# RasPi-BplusHAT_CamSlot.net
KiCad netlist of a schematic drawn in EAGLE
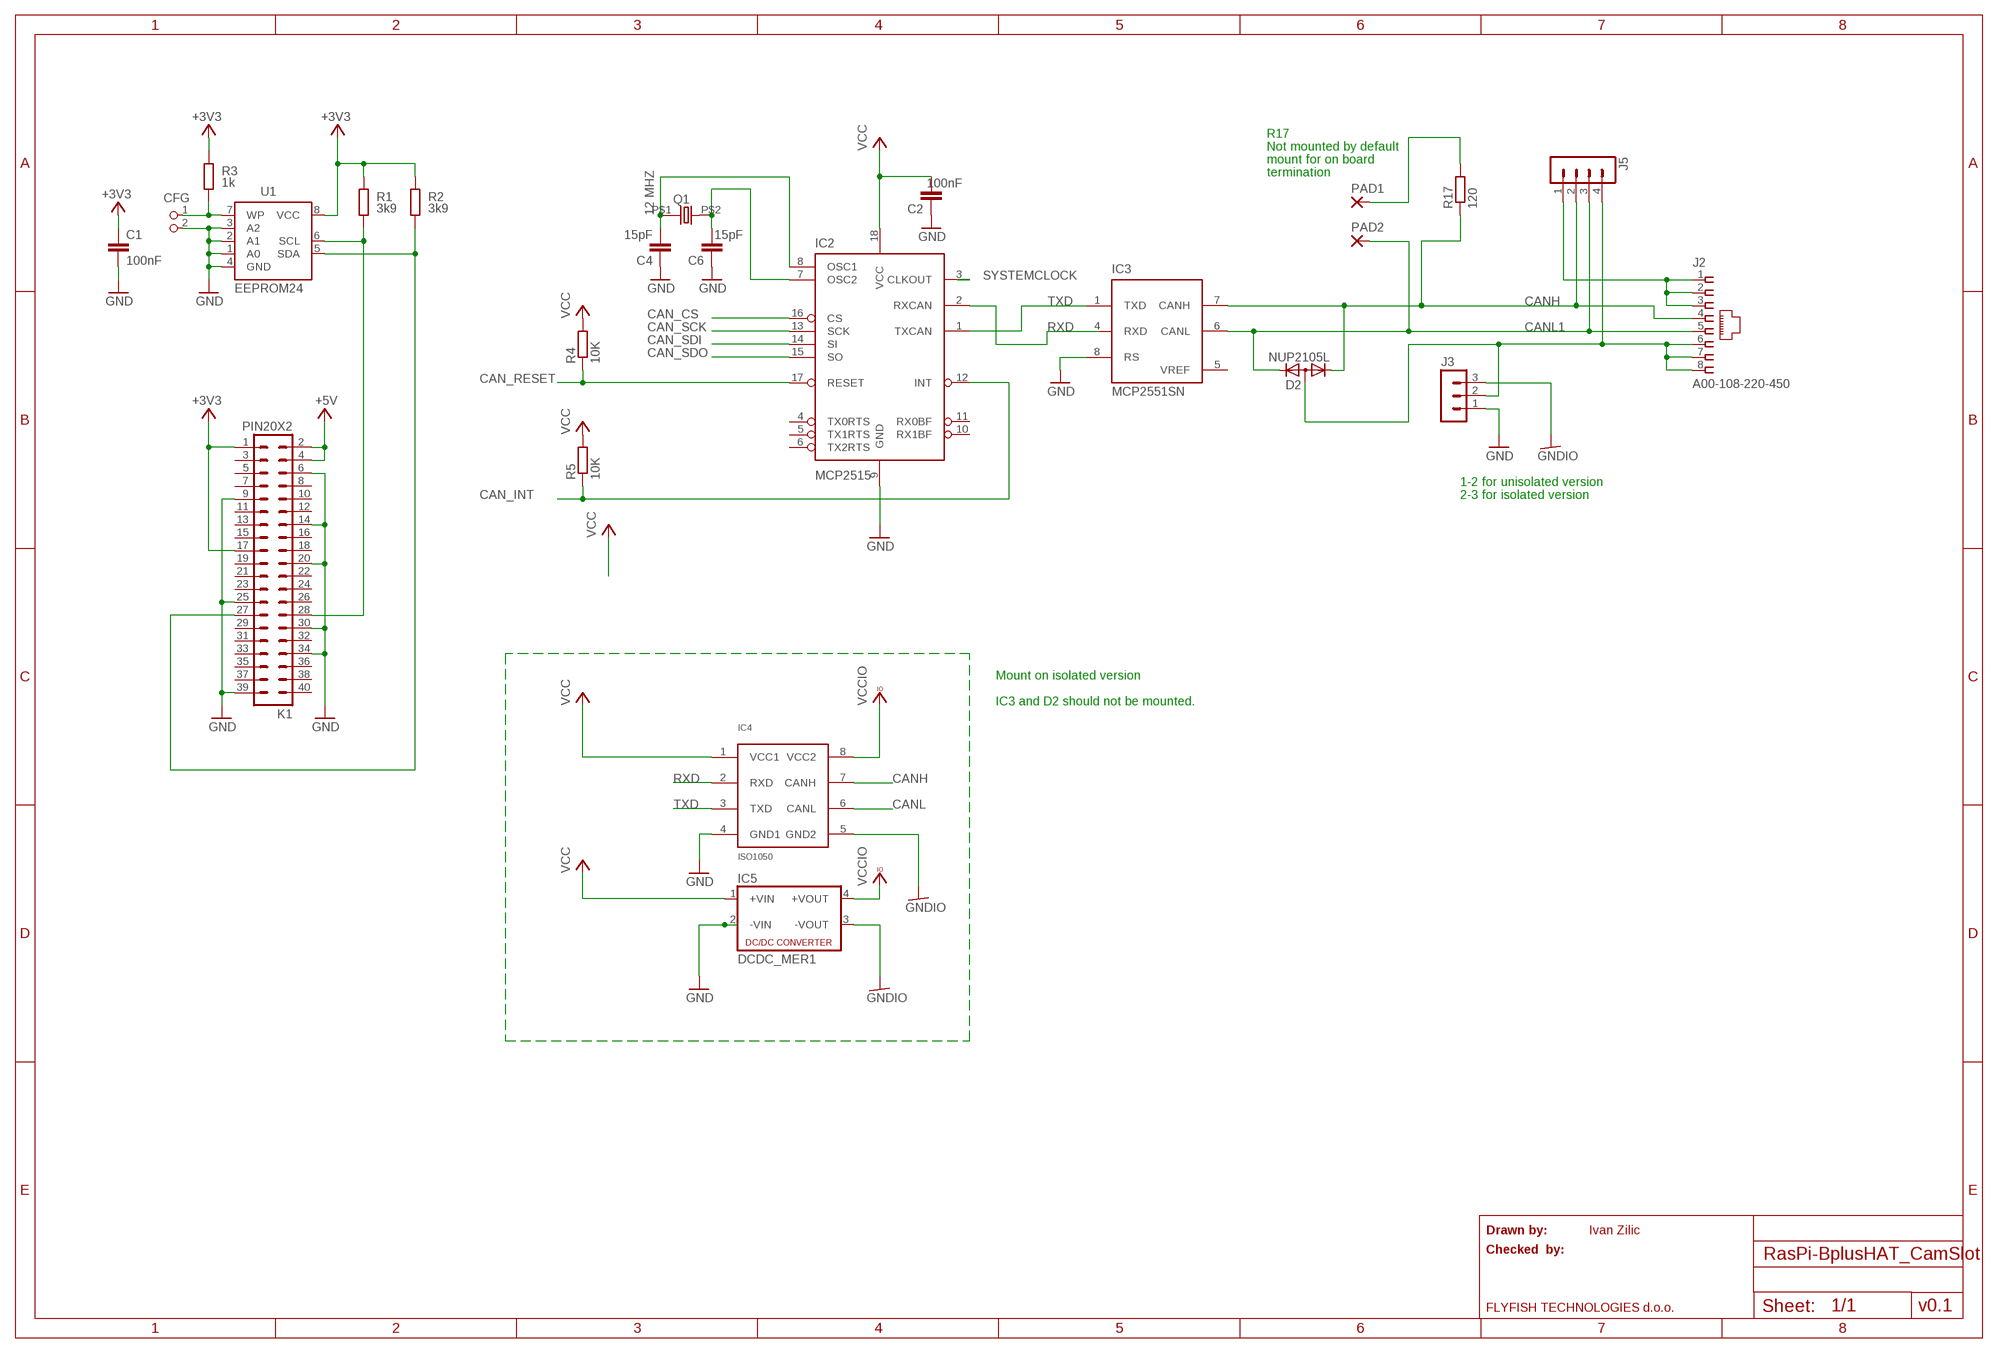
[diagram p0: schematic, sheet 1]

(export (version "E")
  (design (tool "Eeschema 10.0.6"))
  (components
    (comp (ref "C1")
      (value "100nF")
      (footprint "eagle-import:C0805K")
      (libsource (lib "eagle-import") (part "resistor_C-EUC0805K"))
    )
    (comp (ref "C2")
      (value "100nF")
      (footprint "eagle-import:C0805")
      (libsource (lib "eagle-import") (part "C-EUC0805"))
    )
    (comp (ref "C4")
      (value "15pF")
      (footprint "eagle-import:C0805")
      (libsource (lib "eagle-import") (part "C-EUC0805"))
    )
    (comp (ref "C6")
      (value "15pF")
      (footprint "eagle-import:C0805")
      (libsource (lib "eagle-import") (part "C-EUC0805"))
    )
    (comp (ref "CFG")
      (value "PIN2_100")
      (footprint "eagle-import:PIN_W_2")
      (libsource (lib "eagle-import") (part "PIN2_100"))
    )
    (comp (ref "D2")
      (value "NUP2105L")
      (footprint "eagle-import:SOT23")
      (libsource (lib "eagle-import") (part "DIODE-2CA|ACSOT23"))
    )
    (comp (ref "IC2")
      (value "MCP2515")
      (footprint "eagle-import:SO-18W")
      (libsource (lib "eagle-import") (part "MCP2515"))
    )
    (comp (ref "IC3")
      (value "MCP2551SN")
      (footprint "eagle-import:SO-08")
      (libsource (lib "eagle-import") (part "MCP2551SN"))
    )
    (comp (ref "IC4")
      (value "ISO1050")
      (footprint "eagle-import:DUB_PSOP")
      (libsource (lib "eagle-import") (part "ISO1050"))
    )
    (comp (ref "IC5")
      (value "DCDC_MER1")
      (footprint "eagle-import:MER1")
      (libsource (lib "eagle-import") (part "DCDC_MER1"))
    )
    (comp (ref "J2")
      (value "A00-108-220-450")
      (footprint "eagle-import:RJ-45")
      (libsource (lib "eagle-import") (part "A00-108-220-450"))
    )
    (comp (ref "J3")
      (value "MA03-1")
      (footprint "eagle-import:MA03-1")
      (libsource (lib "eagle-import") (part "MA03-1"))
    )
    (comp (ref "J5")
      (value "MA04-1")
      (footprint "eagle-import:MA04-1")
      (libsource (lib "eagle-import") (part "MA04-1"))
    )
    (comp (ref "K1")
      (value "PIN20X2")
      (footprint "eagle-import:PIN_20X2")
      (libsource (lib "eagle-import") (part "PIN20X2"))
    )
    (comp (ref "PAD1")
      (value "1,6/0,8")
      (footprint "eagle-import:1,6_0,8")
      (libsource (lib "eagle-import") (part "1,6/0,8"))
    )
    (comp (ref "PAD2")
      (value "1,6/0,8")
      (footprint "eagle-import:1,6_0,8")
      (libsource (lib "eagle-import") (part "1,6/0,8"))
    )
    (comp (ref "Q1")
      (value "12 MHZ")
      (footprint "eagle-import:9C")
      (libsource (lib "eagle-import") (part "HC-49S"))
    )
    (comp (ref "R1")
      (value "3k9")
      (footprint "eagle-import:M0805")
      (fields (field (name "TOLERANCE") "5%"))
      (libsource (lib "eagle-import") (part "resistor_R-EU_M0805"))
    )
    (comp (ref "R2")
      (value "3k9")
      (footprint "eagle-import:M0805")
      (fields (field (name "TOLERANCE") "5%"))
      (libsource (lib "eagle-import") (part "resistor_R-EU_M0805"))
    )
    (comp (ref "R3")
      (value "1k")
      (footprint "eagle-import:M0805")
      (fields (field (name "TOLERANCE") "5%"))
      (libsource (lib "eagle-import") (part "resistor_R-EU_M0805"))
    )
    (comp (ref "R4")
      (value "10K")
      (footprint "eagle-import:R0805")
      (libsource (lib "eagle-import") (part "R-EU_R0805"))
    )
    (comp (ref "R5")
      (value "10K")
      (footprint "eagle-import:R0805")
      (libsource (lib "eagle-import") (part "R-EU_R0805"))
    )
    (comp (ref "R17")
      (value "120")
      (footprint "eagle-import:R0805")
      (libsource (lib "eagle-import") (part "R-EU_R0805"))
    )
    (comp (ref "U1")
      (value "EEPROM24")
      (footprint "eagle-import:SOIC8")
      (libsource (lib "eagle-import") (part "EEPROM24"))
    )
  )
  (nets
    (net (code "1") (name "+3V3") (class "Default")
      (node (ref "C1") (pin "1") (pinfunction "1_1") (pintype "passive"))
      (node (ref "K1") (pin "1") (pinfunction "1_1") (pintype "passive"))
      (node (ref "K1") (pin "17") (pinfunction "17_17") (pintype "passive"))
      (node (ref "R1") (pin "2") (pinfunction "2_2") (pintype "passive"))
      (node (ref "R2") (pin "2") (pinfunction "2_2") (pintype "passive"))
      (node (ref "R3") (pin "2") (pinfunction "2_2") (pintype "passive"))
      (node (ref "U1") (pin "8") (pinfunction "VCC_8") (pintype "power_in"))
    )
    (net (code "2") (name "+5V") (class "Default")
      (node (ref "K1") (pin "2") (pinfunction "2_2") (pintype "passive"))
      (node (ref "K1") (pin "4") (pinfunction "4_4") (pintype "passive"))
    )
    (net (code "3") (name "/CANH") (class "Default")
      (node (ref "D2") (pin "1") (pinfunction "K1_1") (pintype "passive"))
      (node (ref "IC3") (pin "7") (pinfunction "CANH_7") (pintype "bidirectional"))
      (node (ref "IC4") (pin "7") (pinfunction "CANH_7") (pintype "bidirectional"))
      (node (ref "J2") (pin "4") (pinfunction "4_4") (pintype "passive"))
      (node (ref "J5") (pin "2") (pinfunction "2_2") (pintype "passive"))
      (node (ref "R17") (pin "1") (pinfunction "1_1") (pintype "passive"))
    )
    (net (code "4") (name "/CANL") (class "Default")
      (node (ref "IC4") (pin "6") (pinfunction "CANL_6") (pintype "bidirectional"))
    )
    (net (code "5") (name "/CANL1") (class "Default")
      (node (ref "D2") (pin "2") (pinfunction "K2_2") (pintype "passive"))
      (node (ref "IC3") (pin "6") (pinfunction "CANL_6") (pintype "bidirectional"))
      (node (ref "J2") (pin "5") (pinfunction "5_5") (pintype "passive"))
      (node (ref "J5") (pin "3") (pinfunction "3_3") (pintype "passive"))
      (node (ref "PAD2") (pin "1") (pinfunction "P_1") (pintype "passive"))
    )
    (net (code "6") (name "/CAN_CS") (class "Default")
      (node (ref "IC2") (pin "16") (pinfunction "CS_16") (pintype "input"))
    )
    (net (code "7") (name "/CAN_INT") (class "Default")
      (node (ref "IC2") (pin "12") (pinfunction "INT_12") (pintype "output"))
      (node (ref "R5") (pin "1") (pinfunction "1_1") (pintype "passive"))
    )
    (net (code "8") (name "/CAN_RESET") (class "Default")
      (node (ref "IC2") (pin "17") (pinfunction "RESET_17") (pintype "input"))
      (node (ref "R4") (pin "1") (pinfunction "1_1") (pintype "passive"))
    )
    (net (code "9") (name "/CAN_SCK") (class "Default")
      (node (ref "IC2") (pin "13") (pinfunction "SCK_13") (pintype "input"))
    )
    (net (code "10") (name "/CAN_SDI") (class "Default")
      (node (ref "IC2") (pin "14") (pinfunction "SI_14") (pintype "input"))
    )
    (net (code "11") (name "/CAN_SDO") (class "Default")
      (node (ref "IC2") (pin "15") (pinfunction "SO_15") (pintype "output"))
    )
    (net (code "12") (name "/RXD") (class "Default")
      (node (ref "IC2") (pin "2") (pinfunction "RXCAN_2") (pintype "input"))
      (node (ref "IC4") (pin "2") (pinfunction "RXD_2") (pintype "bidirectional"))
    )
    (net (code "13") (name "/SYSTEMCLOCK") (class "Default")
      (node (ref "IC2") (pin "3") (pinfunction "CLKOUT_3") (pintype "output"))
    )
    (net (code "14") (name "/TXD") (class "Default")
      (node (ref "IC2") (pin "1") (pinfunction "TXCAN_1") (pintype "output"))
      (node (ref "IC3") (pin "1") (pinfunction "TXD_1") (pintype "input"))
      (node (ref "IC4") (pin "3") (pinfunction "TXD_3") (pintype "bidirectional"))
    )
    (net (code "15") (name "/VREF") (class "Default")
      (node (ref "IC3") (pin "5") (pinfunction "VREF_5") (pintype "power_in"))
    )
    (net (code "16") (name "GND") (class "Default")
      (node (ref "C1") (pin "2") (pinfunction "2_2") (pintype "passive"))
      (node (ref "C2") (pin "1") (pinfunction "1_1") (pintype "passive"))
      (node (ref "C4") (pin "1") (pinfunction "1_1") (pintype "passive"))
      (node (ref "C6") (pin "1") (pinfunction "1_1") (pintype "passive"))
      (node (ref "CFG") (pin "2") (pinfunction "2_2") (pintype "passive"))
      (node (ref "IC2") (pin "9") (pinfunction "GND_9") (pintype "power_in"))
      (node (ref "IC3") (pin "8") (pinfunction "RS_8") (pintype "input"))
      (node (ref "IC4") (pin "4") (pinfunction "GND1_4") (pintype "power_in"))
      (node (ref "IC5") (pin "2") (pinfunction "-VIN_2") (pintype "passive"))
      (node (ref "J3") (pin "1") (pinfunction "1_1") (pintype "passive"))
      (node (ref "K1") (pin "14") (pinfunction "14_14") (pintype "passive"))
      (node (ref "K1") (pin "20") (pinfunction "20_20") (pintype "passive"))
      (node (ref "K1") (pin "25") (pinfunction "25_25") (pintype "passive"))
      (node (ref "K1") (pin "30") (pinfunction "30_30") (pintype "passive"))
      (node (ref "K1") (pin "34") (pinfunction "34_34") (pintype "passive"))
      (node (ref "K1") (pin "39") (pinfunction "39_39") (pintype "passive"))
      (node (ref "K1") (pin "6") (pinfunction "6_6") (pintype "passive"))
      (node (ref "K1") (pin "9") (pinfunction "9_9") (pintype "passive"))
      (node (ref "U1") (pin "1") (pinfunction "A0_1") (pintype "input"))
      (node (ref "U1") (pin "2") (pinfunction "A1_2") (pintype "input"))
      (node (ref "U1") (pin "3") (pinfunction "A2_3") (pintype "input"))
      (node (ref "U1") (pin "4") (pinfunction "GND_4") (pintype "power_in"))
    )
    (net (code "17") (name "GNDIO") (class "Default")
      (node (ref "IC4") (pin "5") (pinfunction "GND2_5") (pintype "power_in"))
      (node (ref "IC5") (pin "3") (pinfunction "-VOUT_3") (pintype "passive"))
      (node (ref "J3") (pin "3") (pinfunction "3_3") (pintype "passive"))
    )
    (net (code "18") (name "Net-(D2-A)") (class "Default")
      (node (ref "D2") (pin "3") (pinfunction "A_3") (pintype "passive"))
      (node (ref "J2") (pin "6") (pinfunction "6_6") (pintype "passive"))
      (node (ref "J2") (pin "7") (pinfunction "7_7") (pintype "passive"))
      (node (ref "J2") (pin "8") (pinfunction "8_8") (pintype "passive"))
      (node (ref "J3") (pin "2") (pinfunction "2_2") (pintype "passive"))
      (node (ref "J5") (pin "4") (pinfunction "4_4") (pintype "passive"))
    )
    (net (code "19") (name "Net-(IC2-OSC1)") (class "Default")
      (node (ref "C4") (pin "2") (pinfunction "2_2") (pintype "passive"))
      (node (ref "IC2") (pin "8") (pinfunction "OSC1_8") (pintype "input"))
      (node (ref "Q1") (pin "P$1") (pinfunction "1_P$1") (pintype "passive"))
    )
    (net (code "20") (name "Net-(IC2-OSC2)") (class "Default")
      (node (ref "C6") (pin "2") (pinfunction "2_2") (pintype "passive"))
      (node (ref "IC2") (pin "7") (pinfunction "OSC2_7") (pintype "output"))
      (node (ref "Q1") (pin "P$2") (pinfunction "2_P$2") (pintype "passive"))
    )
    (net (code "21") (name "Net-(J2-Pad1)") (class "Default")
      (node (ref "J2") (pin "1") (pinfunction "1_1") (pintype "passive"))
      (node (ref "J2") (pin "2") (pinfunction "2_2") (pintype "passive"))
      (node (ref "J2") (pin "3") (pinfunction "3_3") (pintype "passive"))
      (node (ref "J5") (pin "1") (pinfunction "1_1") (pintype "passive"))
    )
    (net (code "22") (name "Net-(PAD1-P)") (class "Default")
      (node (ref "PAD1") (pin "1") (pinfunction "P_1") (pintype "passive"))
      (node (ref "R17") (pin "2") (pinfunction "2_2") (pintype "passive"))
    )
    (net (code "23") (name "Net-(U1-SCL)") (class "Default")
      (node (ref "K1") (pin "28") (pinfunction "28_28") (pintype "passive"))
      (node (ref "R1") (pin "1") (pinfunction "1_1") (pintype "passive"))
      (node (ref "U1") (pin "6") (pinfunction "SCL_6") (pintype "input"))
    )
    (net (code "24") (name "Net-(U1-SDA)") (class "Default")
      (node (ref "K1") (pin "27") (pinfunction "27_27") (pintype "passive"))
      (node (ref "R2") (pin "1") (pinfunction "1_1") (pintype "passive"))
      (node (ref "U1") (pin "5") (pinfunction "SDA_5") (pintype "bidirectional"))
    )
    (net (code "25") (name "Net-(U1-WP)") (class "Default")
      (node (ref "CFG") (pin "1") (pinfunction "1_1") (pintype "passive"))
      (node (ref "R3") (pin "1") (pinfunction "1_1") (pintype "passive"))
      (node (ref "U1") (pin "7") (pinfunction "WP_7") (pintype "input"))
    )
    (net (code "26") (name "VCC") (class "Default")
      (node (ref "C2") (pin "2") (pinfunction "2_2") (pintype "passive"))
      (node (ref "IC2") (pin "18") (pinfunction "VCC_18") (pintype "power_in"))
      (node (ref "IC4") (pin "1") (pinfunction "VCC1_1") (pintype "power_in"))
      (node (ref "IC5") (pin "1") (pinfunction "+VIN_1") (pintype "passive"))
      (node (ref "R4") (pin "2") (pinfunction "2_2") (pintype "passive"))
      (node (ref "R5") (pin "2") (pinfunction "2_2") (pintype "passive"))
    )
    (net (code "27") (name "VCCIO") (class "Default")
      (node (ref "IC4") (pin "8") (pinfunction "VCC2_8") (pintype "power_in"))
      (node (ref "IC5") (pin "4") (pinfunction "+VOUT_4") (pintype "passive"))
    )
    (net (code "28") (name "unconnected-(IC2-RX0BF-Pad11)") (class "Default")
      (node (ref "IC2") (pin "11") (pinfunction "RX0BF_11") (pintype "output"))
    )
    (net (code "29") (name "unconnected-(IC2-RX1BF-Pad10)") (class "Default")
      (node (ref "IC2") (pin "10") (pinfunction "RX1BF_10") (pintype "output"))
    )
    (net (code "30") (name "unconnected-(IC2-TX0RTS-Pad4)") (class "Default")
      (node (ref "IC2") (pin "4") (pinfunction "TX0RTS_4") (pintype "input"))
    )
    (net (code "31") (name "unconnected-(IC2-TX1RTS-Pad5)") (class "Default")
      (node (ref "IC2") (pin "5") (pinfunction "TX1RTS_5") (pintype "input"))
    )
    (net (code "32") (name "unconnected-(IC2-TX2RTS-Pad6)") (class "Default")
      (node (ref "IC2") (pin "6") (pinfunction "TX2RTS_6") (pintype "input"))
    )
    (net (code "33") (name "unconnected-(IC3A-RXD-Pad4)") (class "Default")
      (node (ref "IC3") (pin "4") (pinfunction "RXD_4") (pintype "output"))
    )
    (net (code "34") (name "unconnected-(K1-Pad3)") (class "Default")
      (node (ref "K1") (pin "3") (pinfunction "3_3") (pintype "passive"))
    )
    (net (code "35") (name "unconnected-(K1-Pad5)") (class "Default")
      (node (ref "K1") (pin "5") (pinfunction "5_5") (pintype "passive"))
    )
    (net (code "36") (name "unconnected-(K1-Pad7)") (class "Default")
      (node (ref "K1") (pin "7") (pinfunction "7_7") (pintype "passive"))
    )
    (net (code "37") (name "unconnected-(K1-Pad8)") (class "Default")
      (node (ref "K1") (pin "8") (pinfunction "8_8") (pintype "passive"))
    )
    (net (code "38") (name "unconnected-(K1-Pad10)") (class "Default")
      (node (ref "K1") (pin "10") (pinfunction "10_10") (pintype "passive"))
    )
    (net (code "39") (name "unconnected-(K1-Pad11)") (class "Default")
      (node (ref "K1") (pin "11") (pinfunction "11_11") (pintype "passive"))
    )
    (net (code "40") (name "unconnected-(K1-Pad12)") (class "Default")
      (node (ref "K1") (pin "12") (pinfunction "12_12") (pintype "passive"))
    )
    (net (code "41") (name "unconnected-(K1-Pad13)") (class "Default")
      (node (ref "K1") (pin "13") (pinfunction "13_13") (pintype "passive"))
    )
    (net (code "42") (name "unconnected-(K1-Pad15)") (class "Default")
      (node (ref "K1") (pin "15") (pinfunction "15_15") (pintype "passive"))
    )
    (net (code "43") (name "unconnected-(K1-Pad16)") (class "Default")
      (node (ref "K1") (pin "16") (pinfunction "16_16") (pintype "passive"))
    )
    (net (code "44") (name "unconnected-(K1-Pad18)") (class "Default")
      (node (ref "K1") (pin "18") (pinfunction "18_18") (pintype "passive"))
    )
    (net (code "45") (name "unconnected-(K1-Pad19)") (class "Default")
      (node (ref "K1") (pin "19") (pinfunction "19_19") (pintype "passive"))
    )
    (net (code "46") (name "unconnected-(K1-Pad21)") (class "Default")
      (node (ref "K1") (pin "21") (pinfunction "21_21") (pintype "passive"))
    )
    (net (code "47") (name "unconnected-(K1-Pad22)") (class "Default")
      (node (ref "K1") (pin "22") (pinfunction "22_22") (pintype "passive"))
    )
    (net (code "48") (name "unconnected-(K1-Pad23)") (class "Default")
      (node (ref "K1") (pin "23") (pinfunction "23_23") (pintype "passive"))
    )
    (net (code "49") (name "unconnected-(K1-Pad24)") (class "Default")
      (node (ref "K1") (pin "24") (pinfunction "24_24") (pintype "passive"))
    )
    (net (code "50") (name "unconnected-(K1-Pad26)") (class "Default")
      (node (ref "K1") (pin "26") (pinfunction "26_26") (pintype "passive"))
    )
    (net (code "51") (name "unconnected-(K1-Pad29)") (class "Default")
      (node (ref "K1") (pin "29") (pinfunction "29_29") (pintype "passive"))
    )
    (net (code "52") (name "unconnected-(K1-Pad31)") (class "Default")
      (node (ref "K1") (pin "31") (pinfunction "31_31") (pintype "passive"))
    )
    (net (code "53") (name "unconnected-(K1-Pad32)") (class "Default")
      (node (ref "K1") (pin "32") (pinfunction "32_32") (pintype "passive"))
    )
    (net (code "54") (name "unconnected-(K1-Pad33)") (class "Default")
      (node (ref "K1") (pin "33") (pinfunction "33_33") (pintype "passive"))
    )
    (net (code "55") (name "unconnected-(K1-Pad35)") (class "Default")
      (node (ref "K1") (pin "35") (pinfunction "35_35") (pintype "passive"))
    )
    (net (code "56") (name "unconnected-(K1-Pad36)") (class "Default")
      (node (ref "K1") (pin "36") (pinfunction "36_36") (pintype "passive"))
    )
    (net (code "57") (name "unconnected-(K1-Pad37)") (class "Default")
      (node (ref "K1") (pin "37") (pinfunction "37_37") (pintype "passive"))
    )
    (net (code "58") (name "unconnected-(K1-Pad38)") (class "Default")
      (node (ref "K1") (pin "38") (pinfunction "38_38") (pintype "passive"))
    )
    (net (code "59") (name "unconnected-(K1-Pad40)") (class "Default")
      (node (ref "K1") (pin "40") (pinfunction "40_40") (pintype "passive"))
    )
  )
)
